# Spy_Circuits_3-transistor_-_Corr.net
KiCad netlist of a schematic drawn in EAGLE
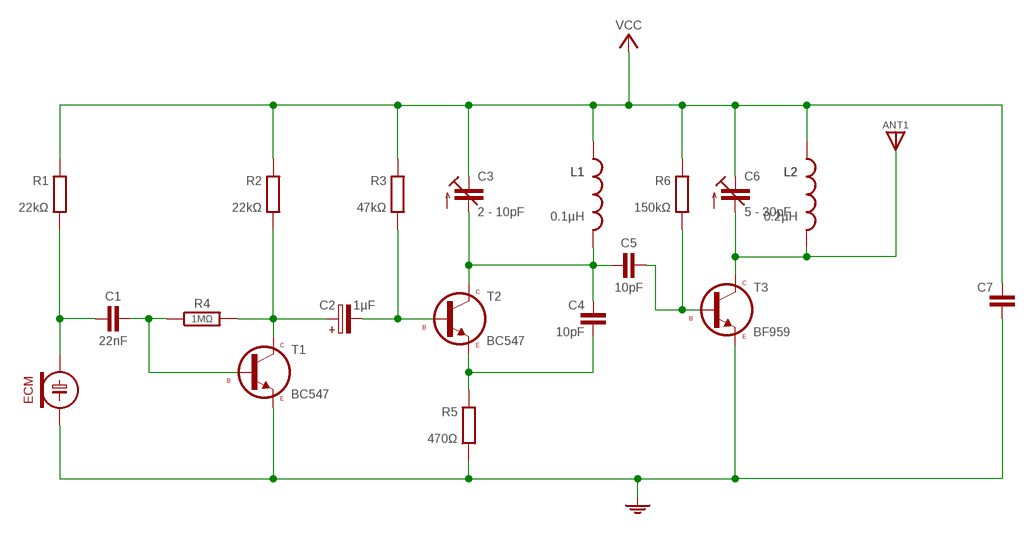
[diagram p0: schematic, sheet 1]

(export (version "E")
  (design (tool "Eeschema 10.0.6"))
  (components
    (comp (ref "ANT1")
      (value "ANT")
      (footprint "eagle-import:SPAD")
      (libsource (lib "eagle-import") (part "ANT"))
    )
    (comp (ref "C1")
      (value "22nF")
      (footprint "eagle-import:C025-015X024")
      (libsource (lib "eagle-import") (part "C-H025-015X024"))
    )
    (comp (ref "C2")
      (value "1µF")
      (footprint "eagle-import:E2,5-3")
      (libsource (lib "eagle-import") (part "CPOL-HE2,5-3"))
    )
    (comp (ref "C3")
      (value "2 - 10pF")
      (footprint "eagle-import:TRIM-2222-808-45")
      (libsource (lib "eagle-import") (part "C-TR-PH201272222-808-45-2PIN"))
    )
    (comp (ref "C4")
      (value "10pF")
      (footprint "eagle-import:C025-015X024_V")
      (libsource (lib "eagle-import") (part "C025-015X024/V"))
    )
    (comp (ref "C5")
      (value "10pF")
      (footprint "eagle-import:C025-015X024")
      (libsource (lib "eagle-import") (part "C-H025-015X024"))
    )
    (comp (ref "C6")
      (value "5 - 30pF")
      (footprint "eagle-import:TRIM-C-BIG")
      (libsource (lib "eagle-import") (part "C-TR-PH20127-C-BIG"))
    )
    (comp (ref "C7")
      (value "C025-015X024/V")
      (footprint "eagle-import:C025-015X024_V")
      (libsource (lib "eagle-import") (part "C025-015X024/V"))
    )
    (comp (ref "ECM1")
      (value "ECM-4")
      (footprint "eagle-import:ECM-4")
      (libsource (lib "eagle-import") (part "ECM-4"))
    )
    (comp (ref "L1")
      (value "0.1µH")
      (footprint "eagle-import:L-04_8V-2-M")
      (libsource (lib "eagle-import") (part "L04/8V-2-M"))
    )
    (comp (ref "L2")
      (value "0.2µH")
      (footprint "eagle-import:L-08-10_5")
      (libsource (lib "eagle-import") (part "L08-10/5"))
    )
    (comp (ref "R1")
      (value "22kΩ")
      (footprint "eagle-import:0204_2")
      (libsource (lib "eagle-import") (part "R0204/2"))
    )
    (comp (ref "R2")
      (value "22kΩ")
      (footprint "eagle-import:0204_10-V")
      (libsource (lib "eagle-import") (part "R0204/10-V"))
    )
    (comp (ref "R3")
      (value "47kΩ")
      (footprint "eagle-import:0204_10")
      (libsource (lib "eagle-import") (part "R0204/10"))
    )
    (comp (ref "R4")
      (value "1MΩ")
      (footprint "eagle-import:0202_2V")
      (libsource (lib "eagle-import") (part "R-H0202/2V"))
    )
    (comp (ref "R5")
      (value "470Ω")
      (footprint "eagle-import:0204_2")
      (libsource (lib "eagle-import") (part "R0204/2"))
    )
    (comp (ref "R6")
      (value "150kΩ")
      (footprint "eagle-import:0204_2")
      (libsource (lib "eagle-import") (part "R0204/2"))
    )
    (comp (ref "S1")
      (value "VCC_GNDL")
      (footprint "eagle-import:SPAD-+")
      (libsource (lib "eagle-import") (part "VCC_GNDL"))
    )
    (comp (ref "T1")
      (value "BC547")
      (footprint "eagle-import:TO92")
      (libsource (lib "eagle-import") (part "BC547"))
    )
    (comp (ref "T2")
      (value "BC547")
      (footprint "eagle-import:TO92")
      (libsource (lib "eagle-import") (part "BC547"))
    )
    (comp (ref "T3")
      (value "BF959")
      (footprint "eagle-import:TO92-CEB")
      (libsource (lib "eagle-import") (part "BF959"))
    )
  )
  (nets
    (net (code "1") (name "Net-(C3-A)") (class "Default")
      (node (ref "C3") (pin "2") (pinfunction "A_2") (pintype "passive"))
      (node (ref "C4") (pin "1") (pinfunction "1_1") (pintype "passive"))
      (node (ref "C5") (pin "1") (pinfunction "1_1") (pintype "passive"))
      (node (ref "L1") (pin "1") (pinfunction "2_1") (pintype "passive"))
      (node (ref "T2") (pin "1") (pinfunction "C_1") (pintype "passive"))
    )
    (net (code "2") (name "Net-(C3-E)") (class "Default")
      (node (ref "C3") (pin "1") (pinfunction "E_1") (pintype "passive"))
      (node (ref "C6") (pin "P$3") (pinfunction "E_P$3") (pintype "passive"))
      (node (ref "C7") (pin "1") (pinfunction "1_1") (pintype "passive"))
      (node (ref "L1") (pin "2") (pinfunction "1_2") (pintype "passive"))
      (node (ref "L2") (pin "1") (pinfunction "1_1") (pintype "passive"))
      (node (ref "R1") (pin "1") (pinfunction "2_1") (pintype "passive"))
      (node (ref "R2") (pin "1") (pinfunction "2_1") (pintype "passive"))
      (node (ref "R3") (pin "1") (pinfunction "2_1") (pintype "passive"))
      (node (ref "R6") (pin "1") (pinfunction "2_1") (pintype "passive"))
      (node (ref "S1") (pin "2") (pinfunction "VCC_2") (pintype "power_in"))
    )
    (net (code "3") (name "Net-(C6-A)") (class "Default")
      (node (ref "ANT1") (pin "1") (pinfunction "1_1") (pintype "output"))
      (node (ref "C6") (pin "P$1") (pinfunction "A_P$1") (pintype "passive"))
      (node (ref "L2") (pin "2") (pinfunction "2_2") (pintype "passive"))
      (node (ref "T3") (pin "C") (pinfunction "C_C") (pintype "passive"))
    )
    (net (code "4") (name "Net-(ECM1-+)") (class "Default")
      (node (ref "C1") (pin "1") (pinfunction "1_1") (pintype "passive"))
      (node (ref "ECM1") (pin "1") (pinfunction "+_1") (pintype "passive"))
      (node (ref "R1") (pin "2") (pinfunction "1_2") (pintype "passive"))
    )
    (net (code "5") (name "Net-(ECM1--)") (class "Default")
      (node (ref "C7") (pin "2") (pinfunction "2_2") (pintype "passive"))
      (node (ref "ECM1") (pin "2") (pinfunction "-_2") (pintype "passive"))
      (node (ref "R5") (pin "2") (pinfunction "1_2") (pintype "passive"))
      (node (ref "S1") (pin "1") (pinfunction "GND_1") (pintype "power_in"))
      (node (ref "T1") (pin "3") (pinfunction "E_3") (pintype "passive"))
      (node (ref "T3") (pin "E") (pinfunction "E_E") (pintype "passive"))
    )
    (net (code "6") (name "Net-(R2-1)") (class "Default")
      (node (ref "C2") (pin "+") (pinfunction "+_+") (pintype "passive"))
      (node (ref "R2") (pin "2") (pinfunction "1_2") (pintype "passive"))
      (node (ref "R4") (pin "2") (pinfunction "2_2") (pintype "passive"))
      (node (ref "T1") (pin "1") (pinfunction "C_1") (pintype "passive"))
    )
    (net (code "7") (name "Net-(R3-1)") (class "Default")
      (node (ref "C2") (pin "-") (pinfunction "-_-") (pintype "passive"))
      (node (ref "R3") (pin "2") (pinfunction "1_2") (pintype "passive"))
      (node (ref "T2") (pin "2") (pinfunction "B_2") (pintype "passive"))
    )
    (net (code "8") (name "Net-(R5-2)") (class "Default")
      (node (ref "C4") (pin "2") (pinfunction "2_2") (pintype "passive"))
      (node (ref "R5") (pin "1") (pinfunction "2_1") (pintype "passive"))
      (node (ref "T2") (pin "3") (pinfunction "E_3") (pintype "passive"))
    )
    (net (code "9") (name "Net-(R6-1)") (class "Default")
      (node (ref "C5") (pin "2") (pinfunction "2_2") (pintype "passive"))
      (node (ref "R6") (pin "2") (pinfunction "1_2") (pintype "passive"))
      (node (ref "T3") (pin "B") (pinfunction "B_B") (pintype "passive"))
    )
    (net (code "10") (name "Net-(T1-B)") (class "Default")
      (node (ref "C1") (pin "2") (pinfunction "2_2") (pintype "passive"))
      (node (ref "R4") (pin "1") (pinfunction "1_1") (pintype "passive"))
      (node (ref "T1") (pin "2") (pinfunction "B_2") (pintype "passive"))
    )
  )
)
